# LCD_BackPack_wider_one_sided.net
KiCad netlist of a schematic drawn in EAGLE
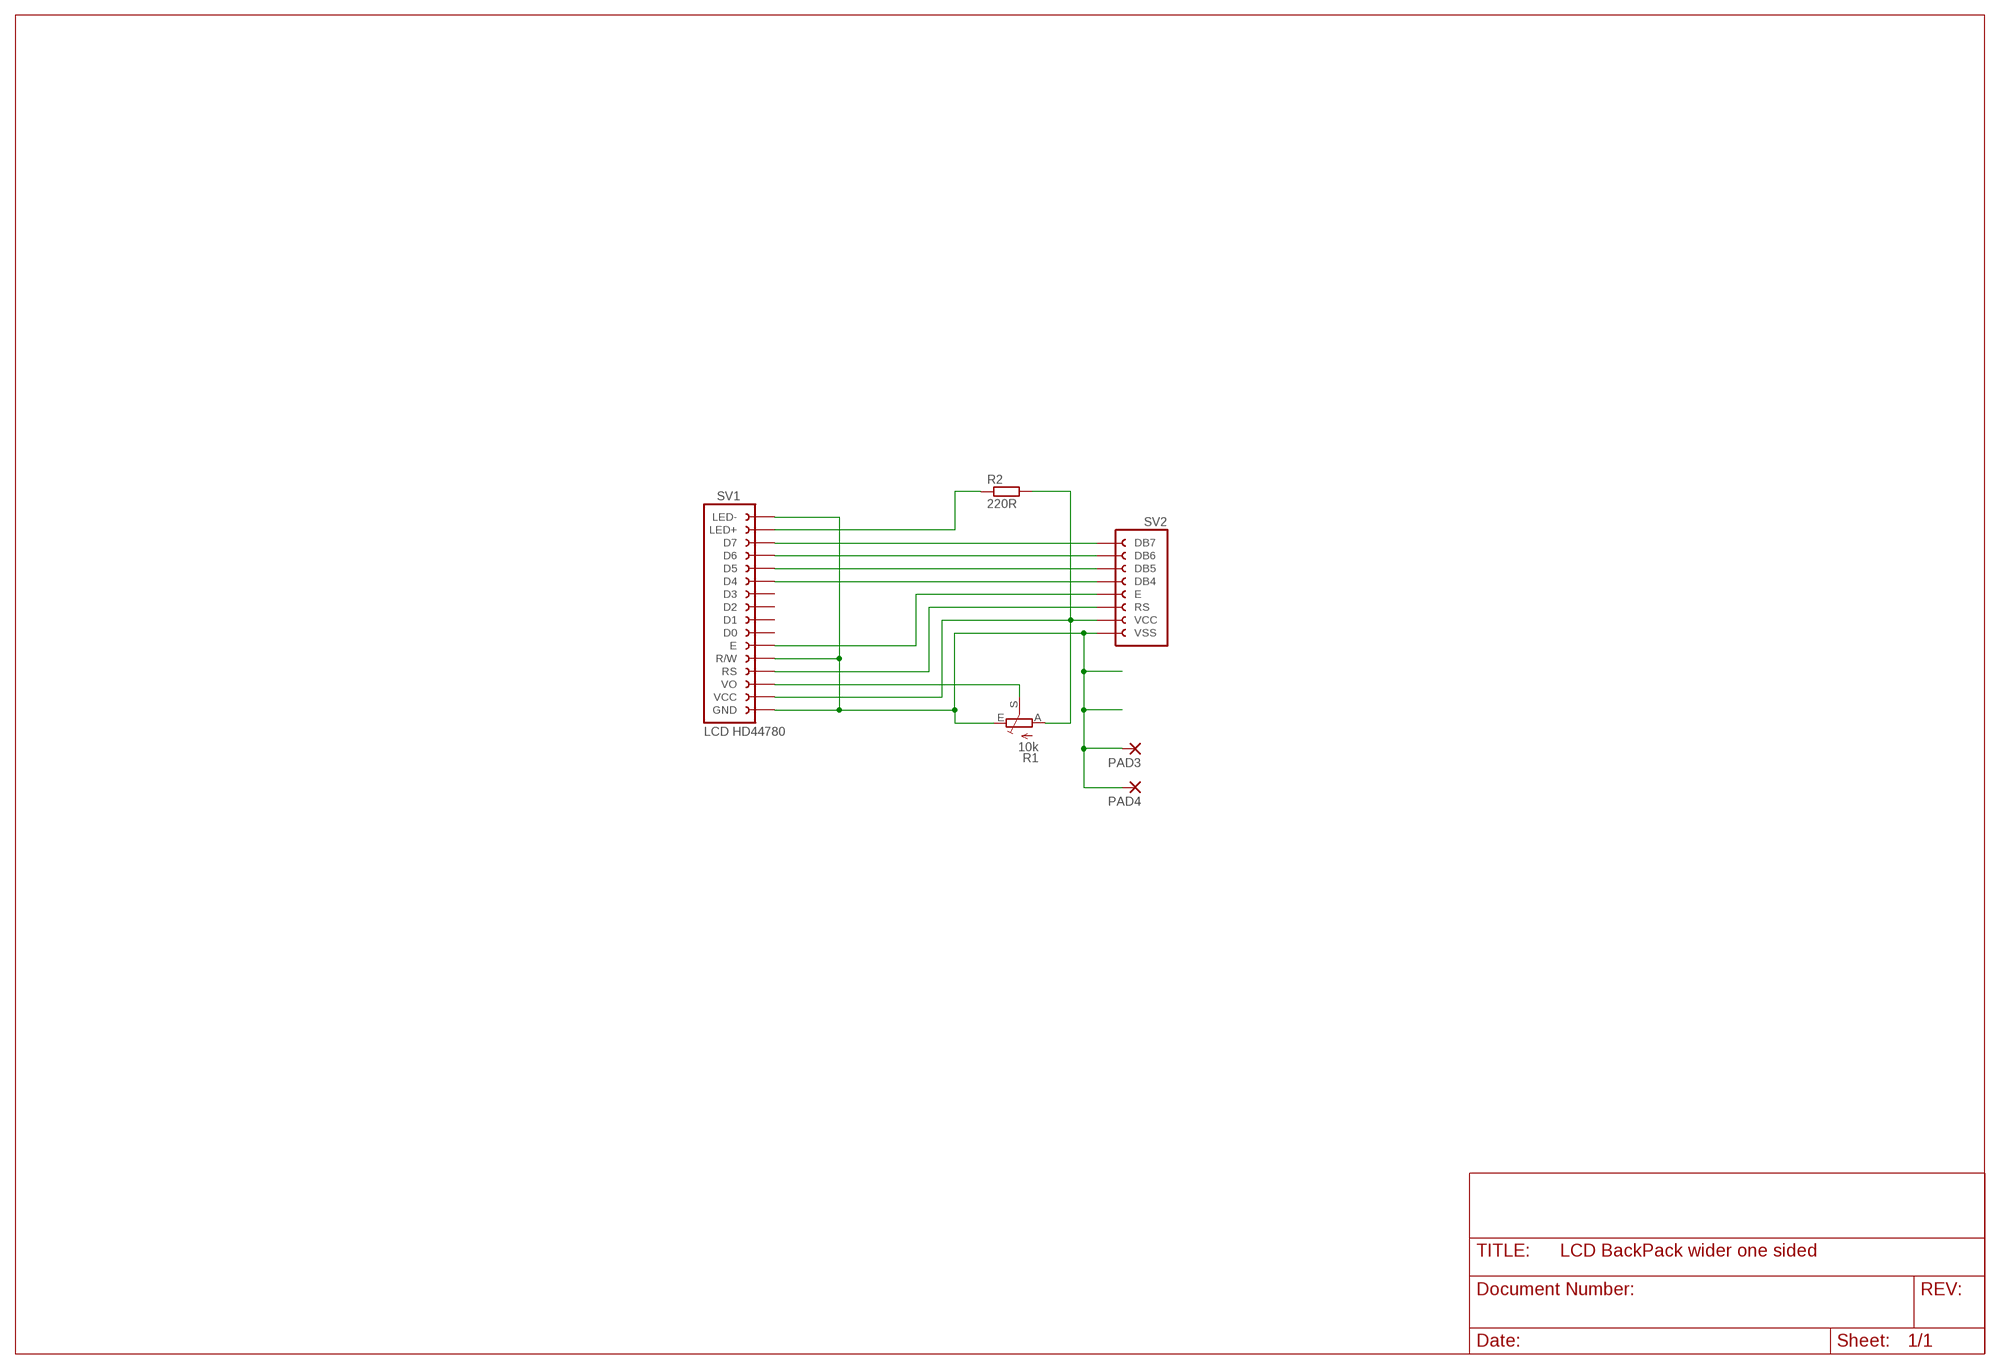
[diagram p0: schematic, sheet 1]

(export (version "E")
  (design (tool "Eeschema 10.0.6"))
  (components
    (comp (ref "PAD3")
      (value "1,6/0,8")
      (footprint "eagle-import:1,6_0,8")
      (libsource (lib "eagle-import") (part "1,6/0,8"))
    )
    (comp (ref "PAD4")
      (value "1,6/0,8")
      (footprint "eagle-import:1,6_0,8")
      (libsource (lib "eagle-import") (part "1,6/0,8"))
    )
    (comp (ref "R1")
      (value "10k")
      (footprint "eagle-import:CA6V")
      (libsource (lib "eagle-import") (part "POTENTIOMETER_CA6VCA6V"))
    )
    (comp (ref "R2")
      (value "220R")
      (footprint "eagle-import:0204_7")
      (libsource (lib "eagle-import") (part "R-EU_0204/7"))
    )
    (comp (ref "SV1")
      (value "LCD-HD44780-16-PIN_FEMALE_HEADER")
      (footprint "eagle-import:LCD-HD44780-16-PIN_FEMALE_HEADER")
      (libsource (lib "eagle-import") (part "LCD-HD44780-16-PIN_FEMALE_HEADER"))
    )
    (comp (ref "SV2")
      (value "LCD-CONTROL_8-PIN_FEMALE_HEADER")
      (footprint "eagle-import:LCD-CONTROL_8-PIN_FEMALE_HEADER")
      (libsource (lib "eagle-import") (part "LCD-CONTROL_8-PIN_FEMALE_HEADER"))
    )
  )
  (nets
    (net (code "1") (name "Net-(PAD3-P)") (class "Default")
      (node (ref "PAD3") (pin "1") (pinfunction "P_1") (pintype "passive"))
      (node (ref "PAD4") (pin "1") (pinfunction "P_1") (pintype "passive"))
      (node (ref "R1") (pin "E") (pinfunction "E_E") (pintype "passive"))
      (node (ref "SV1") (pin "GND") (pinfunction "GND_GND") (pintype "passive"))
      (node (ref "SV1") (pin "LED-") (pinfunction "LED-_LED-") (pintype "passive"))
      (node (ref "SV1") (pin "R/W") (pinfunction "R/W_R/W") (pintype "passive"))
      (node (ref "SV2") (pin "VSS") (pinfunction "VSS_VSS") (pintype "passive"))
    )
    (net (code "2") (name "Net-(R1-PadA)") (class "Default")
      (node (ref "R1") (pin "A") (pinfunction "A_A") (pintype "passive"))
      (node (ref "R2") (pin "2") (pinfunction "2_2") (pintype "passive"))
      (node (ref "SV1") (pin "VCC") (pinfunction "VCC_VCC") (pintype "passive"))
      (node (ref "SV2") (pin "VCC") (pinfunction "VCC_VCC") (pintype "passive"))
    )
    (net (code "3") (name "Net-(R1-PadS)") (class "Default")
      (node (ref "R1") (pin "S") (pinfunction "S_S") (pintype "passive"))
      (node (ref "SV1") (pin "VO") (pinfunction "VO_VO") (pintype "passive"))
    )
    (net (code "4") (name "Net-(R2-Pad1)") (class "Default")
      (node (ref "R2") (pin "1") (pinfunction "1_1") (pintype "passive"))
      (node (ref "SV1") (pin "LED+") (pinfunction "LED+_LED+") (pintype "passive"))
    )
    (net (code "5") (name "Net-(SV1-PadD4)") (class "Default")
      (node (ref "SV1") (pin "D4") (pinfunction "D4_D4") (pintype "passive"))
      (node (ref "SV2") (pin "DB4") (pinfunction "DB4_DB4") (pintype "passive"))
    )
    (net (code "6") (name "Net-(SV1-PadD5)") (class "Default")
      (node (ref "SV1") (pin "D5") (pinfunction "D5_D5") (pintype "passive"))
      (node (ref "SV2") (pin "DB5") (pinfunction "DB5_DB5") (pintype "passive"))
    )
    (net (code "7") (name "Net-(SV1-PadD6)") (class "Default")
      (node (ref "SV1") (pin "D6") (pinfunction "D6_D6") (pintype "passive"))
      (node (ref "SV2") (pin "DB6") (pinfunction "DB6_DB6") (pintype "passive"))
    )
    (net (code "8") (name "Net-(SV1-PadD7)") (class "Default")
      (node (ref "SV1") (pin "D7") (pinfunction "D7_D7") (pintype "passive"))
      (node (ref "SV2") (pin "DB7") (pinfunction "DB7_DB7") (pintype "passive"))
    )
    (net (code "9") (name "Net-(SV1-PadE)") (class "Default")
      (node (ref "SV1") (pin "E") (pinfunction "E_E") (pintype "passive"))
      (node (ref "SV2") (pin "E") (pinfunction "E_E") (pintype "passive"))
    )
    (net (code "10") (name "Net-(SV1-PadRS)") (class "Default")
      (node (ref "SV1") (pin "RS") (pinfunction "RS_RS") (pintype "passive"))
      (node (ref "SV2") (pin "RS") (pinfunction "RS_RS") (pintype "passive"))
    )
    (net (code "11") (name "unconnected-(SV1-PadD0)") (class "Default")
      (node (ref "SV1") (pin "D0") (pinfunction "D0_D0") (pintype "passive"))
    )
    (net (code "12") (name "unconnected-(SV1-PadD1)") (class "Default")
      (node (ref "SV1") (pin "D1") (pinfunction "D1_D1") (pintype "passive"))
    )
    (net (code "13") (name "unconnected-(SV1-PadD2)") (class "Default")
      (node (ref "SV1") (pin "D2") (pinfunction "D2_D2") (pintype "passive"))
    )
    (net (code "14") (name "unconnected-(SV1-PadD3)") (class "Default")
      (node (ref "SV1") (pin "D3") (pinfunction "D3_D3") (pintype "passive"))
    )
  )
)
